# pcb-56dp30a-gain.net
KiCad netlist of a schematic drawn in EAGLE
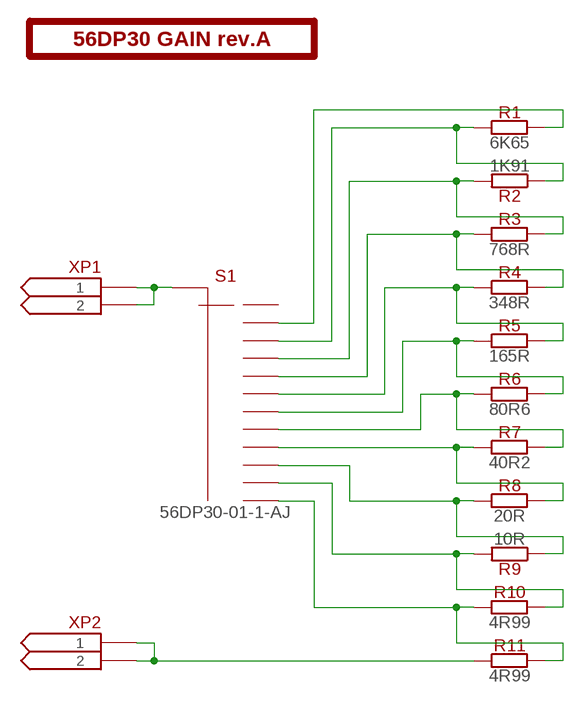
[diagram p0: schematic, sheet 1]

(export (version "E")
  (design (tool "Eeschema 10.0.6"))
  (components
    (comp (ref "PCB1")
      (value "56DP30 GAIN rev.A")
      (footprint "eagle-import:F-LOGO")
      (libsource (lib "eagle-import") (part "GENERIC-LOGO"))
    )
    (comp (ref "R1")
      (value "6K65")
      (footprint "eagle-import:R-0805")
      (libsource (lib "eagle-import") (part "?6K65"))
    )
    (comp (ref "R2")
      (value "1K91")
      (footprint "eagle-import:R-0805")
      (libsource (lib "eagle-import") (part "?1K91"))
    )
    (comp (ref "R3")
      (value "768R")
      (footprint "eagle-import:R-0805")
      (libsource (lib "eagle-import") (part "?768R"))
    )
    (comp (ref "R4")
      (value "348R")
      (footprint "eagle-import:R-0805")
      (libsource (lib "eagle-import") (part "?348R"))
    )
    (comp (ref "R5")
      (value "165R")
      (footprint "eagle-import:R-0805")
      (libsource (lib "eagle-import") (part "?165R"))
    )
    (comp (ref "R6")
      (value "80R6")
      (footprint "eagle-import:R-0805")
      (libsource (lib "eagle-import") (part "?80R6"))
    )
    (comp (ref "R7")
      (value "40R2")
      (footprint "eagle-import:R-0805")
      (libsource (lib "eagle-import") (part "?40R2"))
    )
    (comp (ref "R8")
      (value "20R")
      (footprint "eagle-import:R-0805")
      (libsource (lib "eagle-import") (part "?20R"))
    )
    (comp (ref "R9")
      (value "10R")
      (footprint "eagle-import:R-0805")
      (libsource (lib "eagle-import") (part "?10R"))
    )
    (comp (ref "R10")
      (value "4R99")
      (footprint "eagle-import:R-0805")
      (libsource (lib "eagle-import") (part "?4R99"))
    )
    (comp (ref "R11")
      (value "4R99")
      (footprint "eagle-import:R-0805")
      (libsource (lib "eagle-import") (part "?4R99"))
    )
    (comp (ref "S1")
      (value "56DP30-01-1-AJ")
      (footprint "eagle-import:56DP30-01-1")
      (libsource (lib "eagle-import") (part "56DP30-01-1-AJ"))
    )
    (comp (ref "XP1")
      (value "CONN-2-NORMAL")
      (footprint "eagle-import:ML2")
      (libsource (lib "eagle-import") (part "CONN-2-?NORMAL"))
    )
    (comp (ref "XP2")
      (value "CONN-2-NORMAL")
      (footprint "eagle-import:ML2")
      (libsource (lib "eagle-import") (part "CONN-2-?NORMAL"))
    )
  )
  (nets
    (net (code "1") (name "Net-(R1-Pad1)") (class "Default")
      (node (ref "R1") (pin "1") (pinfunction "1_1") (pintype "passive"))
      (node (ref "R2") (pin "1") (pinfunction "1_1") (pintype "passive"))
      (node (ref "S1") (pin "3") (pinfunction "3_3") (pintype "passive"))
    )
    (net (code "2") (name "Net-(R1-Pad2)") (class "Default")
      (node (ref "R1") (pin "2") (pinfunction "2_2") (pintype "passive"))
      (node (ref "S1") (pin "2") (pinfunction "2_2") (pintype "passive"))
    )
    (net (code "3") (name "Net-(R2-Pad2)") (class "Default")
      (node (ref "R2") (pin "2") (pinfunction "2_2") (pintype "passive"))
      (node (ref "R3") (pin "2") (pinfunction "2_2") (pintype "passive"))
      (node (ref "S1") (pin "4") (pinfunction "4_4") (pintype "passive"))
    )
    (net (code "4") (name "Net-(R3-Pad1)") (class "Default")
      (node (ref "R3") (pin "1") (pinfunction "1_1") (pintype "passive"))
      (node (ref "R4") (pin "2") (pinfunction "2_2") (pintype "passive"))
      (node (ref "S1") (pin "5") (pinfunction "5_5") (pintype "passive"))
    )
    (net (code "5") (name "Net-(R4-Pad1)") (class "Default")
      (node (ref "R4") (pin "1") (pinfunction "1_1") (pintype "passive"))
      (node (ref "R5") (pin "2") (pinfunction "2_2") (pintype "passive"))
      (node (ref "S1") (pin "6") (pinfunction "6_6") (pintype "passive"))
    )
    (net (code "6") (name "Net-(R5-Pad1)") (class "Default")
      (node (ref "R5") (pin "1") (pinfunction "1_1") (pintype "passive"))
      (node (ref "R6") (pin "2") (pinfunction "2_2") (pintype "passive"))
      (node (ref "S1") (pin "7") (pinfunction "7_7") (pintype "passive"))
    )
    (net (code "7") (name "Net-(R6-Pad1)") (class "Default")
      (node (ref "R6") (pin "1") (pinfunction "1_1") (pintype "passive"))
      (node (ref "R7") (pin "2") (pinfunction "2_2") (pintype "passive"))
      (node (ref "S1") (pin "8") (pinfunction "8_8") (pintype "passive"))
    )
    (net (code "8") (name "Net-(R7-Pad1)") (class "Default")
      (node (ref "R7") (pin "1") (pinfunction "1_1") (pintype "passive"))
      (node (ref "R8") (pin "2") (pinfunction "2_2") (pintype "passive"))
      (node (ref "S1") (pin "9") (pinfunction "9_9") (pintype "passive"))
    )
    (net (code "9") (name "Net-(R8-Pad1)") (class "Default")
      (node (ref "R8") (pin "1") (pinfunction "1_1") (pintype "passive"))
      (node (ref "R9") (pin "1") (pinfunction "1_1") (pintype "passive"))
      (node (ref "S1") (pin "10") (pinfunction "10_10") (pintype "passive"))
    )
    (net (code "10") (name "Net-(R10-Pad1)") (class "Default")
      (node (ref "R10") (pin "1") (pinfunction "1_1") (pintype "passive"))
      (node (ref "R11") (pin "2") (pinfunction "2_2") (pintype "passive"))
      (node (ref "S1") (pin "12") (pinfunction "12_12") (pintype "passive"))
    )
    (net (code "11") (name "Net-(R10-Pad2)") (class "Default")
      (node (ref "R10") (pin "2") (pinfunction "2_2") (pintype "passive"))
      (node (ref "R9") (pin "2") (pinfunction "2_2") (pintype "passive"))
      (node (ref "S1") (pin "11") (pinfunction "11_11") (pintype "passive"))
    )
    (net (code "12") (name "Net-(R11-Pad1)") (class "Default")
      (node (ref "R11") (pin "1") (pinfunction "1_1") (pintype "passive"))
      (node (ref "XP2") (pin "1") (pinfunction "1_1") (pintype "passive"))
      (node (ref "XP2") (pin "2") (pinfunction "2_2") (pintype "passive"))
    )
    (net (code "13") (name "Net-(S1-CM)") (class "Default")
      (node (ref "S1") (pin "C") (pinfunction "CM_C") (pintype "passive"))
      (node (ref "XP1") (pin "1") (pinfunction "1_1") (pintype "passive"))
      (node (ref "XP1") (pin "2") (pinfunction "2_2") (pintype "passive"))
    )
    (net (code "14") (name "unconnected-(S1-Pad1)") (class "Default")
      (node (ref "S1") (pin "1") (pinfunction "1_1") (pintype "passive"))
    )
  )
)
